# driver.net
KiCad netlist of a schematic drawn in EAGLE
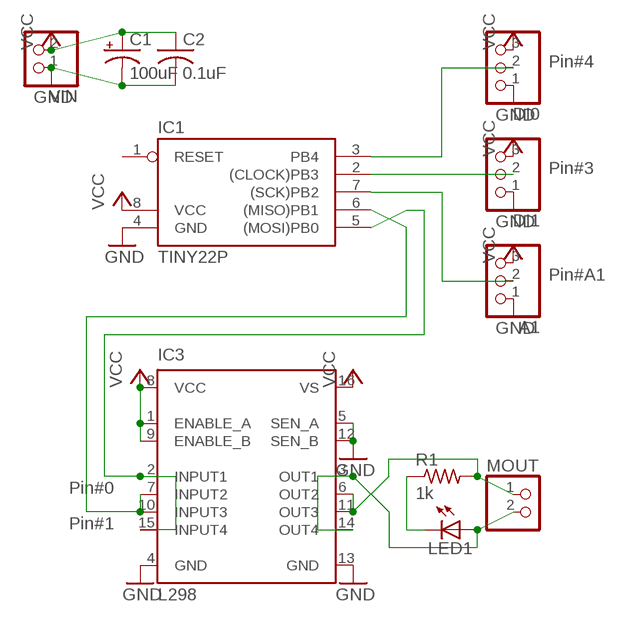
[diagram p0: schematic, sheet 1]

(export (version "E")
  (design (tool "Eeschema 10.0.6"))
  (components
    (comp (ref "A1")
      (value "PINHD-1X3")
      (footprint "eagle-import:1X03")
      (libsource (lib "eagle-import") (part "PINHD-1X3"))
    )
    (comp (ref "C1")
      (value "100uF")
      (footprint "eagle-import:E2,5-6E")
      (libsource (lib "eagle-import") (part "CPOL-USE2,5-6E"))
    )
    (comp (ref "C2")
      (value "0.1uF")
      (footprint "eagle-import:C025-025X050")
      (libsource (lib "eagle-import") (part "C-US025-025X050"))
    )
    (comp (ref "DI0")
      (value "PINHD-1X3")
      (footprint "eagle-import:1X03")
      (libsource (lib "eagle-import") (part "PINHD-1X3"))
    )
    (comp (ref "DI1")
      (value "PINHD-1X3")
      (footprint "eagle-import:1X03")
      (libsource (lib "eagle-import") (part "PINHD-1X3"))
    )
    (comp (ref "IC1")
      (value "TINY22P")
      (footprint "eagle-import:DIL08")
      (libsource (lib "eagle-import") (part "TINY22P"))
    )
    (comp (ref "IC3")
      (value "L298")
      (footprint "eagle-import:DIL16")
      (libsource (lib "eagle-import") (part "L298"))
    )
    (comp (ref "LED1")
      (value "LED5MM")
      (footprint "eagle-import:LED5MM")
      (libsource (lib "eagle-import") (part "LED5MM"))
    )
    (comp (ref "MOUT")
      (value "PINHD-1X2")
      (footprint "eagle-import:1X02")
      (libsource (lib "eagle-import") (part "PINHD-1X2"))
    )
    (comp (ref "R1")
      (value "1k")
      (footprint "eagle-import:0204V")
      (libsource (lib "eagle-import") (part "R-US_0204/2V"))
    )
    (comp (ref "VIN")
      (value "PINHD-1X2")
      (footprint "eagle-import:1X02")
      (libsource (lib "eagle-import") (part "PINHD-1X2"))
    )
  )
  (nets
    (net (code "1") (name "GND") (class "Default")
      (node (ref "A1") (pin "1") (pinfunction "1_1") (pintype "passive"))
      (node (ref "C1") (pin "-") (pinfunction "-_-") (pintype "passive"))
      (node (ref "C2") (pin "2") (pinfunction "2_2") (pintype "passive"))
      (node (ref "DI0") (pin "1") (pinfunction "1_1") (pintype "passive"))
      (node (ref "DI1") (pin "1") (pinfunction "1_1") (pintype "passive"))
      (node (ref "IC1") (pin "4") (pinfunction "GND_4") (pintype "power_in"))
      (node (ref "IC3") (pin "12") (pinfunction "SEN_B_12") (pintype "input"))
      (node (ref "IC3") (pin "13") (pinfunction "GND_13") (pintype "power_in"))
      (node (ref "IC3") (pin "4") (pinfunction "GND_4") (pintype "power_in"))
      (node (ref "IC3") (pin "5") (pinfunction "SEN_A_5") (pintype "input"))
      (node (ref "VIN") (pin "1") (pinfunction "1_1") (pintype "passive"))
    )
    (net (code "2") (name "Net-(IC1-(CLOCK)PB3)") (class "Default")
      (node (ref "DI1") (pin "2") (pinfunction "2_2") (pintype "passive"))
      (node (ref "IC1") (pin "2") (pinfunction "(CLOCK)PB3_2") (pintype "bidirectional"))
    )
    (net (code "3") (name "Net-(IC1-(MISO)PB1)") (class "Default")
      (node (ref "IC1") (pin "6") (pinfunction "(MISO)PB1_6") (pintype "bidirectional"))
      (node (ref "IC3") (pin "10") (pinfunction "INPUT3_10") (pintype "input"))
      (node (ref "IC3") (pin "7") (pinfunction "INPUT2_7") (pintype "input"))
    )
    (net (code "4") (name "Net-(IC1-(MOSI)PB0)") (class "Default")
      (node (ref "IC1") (pin "5") (pinfunction "(MOSI)PB0_5") (pintype "bidirectional"))
      (node (ref "IC3") (pin "15") (pinfunction "INPUT4_15") (pintype "input"))
      (node (ref "IC3") (pin "2") (pinfunction "INPUT1_2") (pintype "input"))
    )
    (net (code "5") (name "Net-(IC1-(SCK)PB2)") (class "Default")
      (node (ref "A1") (pin "2") (pinfunction "2_2") (pintype "passive"))
      (node (ref "IC1") (pin "7") (pinfunction "(SCK)PB2_7") (pintype "bidirectional"))
    )
    (net (code "6") (name "Net-(IC1-PB4)") (class "Default")
      (node (ref "DI0") (pin "2") (pinfunction "2_2") (pintype "passive"))
      (node (ref "IC1") (pin "3") (pinfunction "PB4_3") (pintype "bidirectional"))
    )
    (net (code "7") (name "Net-(IC3-OUT1)") (class "Default")
      (node (ref "IC3") (pin "14") (pinfunction "OUT4_14") (pintype "output"))
      (node (ref "IC3") (pin "3") (pinfunction "OUT1_3") (pintype "output"))
      (node (ref "LED1") (pin "A") (pinfunction "A_A") (pintype "passive"))
      (node (ref "MOUT") (pin "2") (pinfunction "2_2") (pintype "passive"))
    )
    (net (code "8") (name "Net-(IC3-OUT2)") (class "Default")
      (node (ref "IC3") (pin "11") (pinfunction "OUT3_11") (pintype "output"))
      (node (ref "IC3") (pin "6") (pinfunction "OUT2_6") (pintype "output"))
      (node (ref "MOUT") (pin "1") (pinfunction "1_1") (pintype "passive"))
      (node (ref "R1") (pin "2") (pinfunction "2_2") (pintype "passive"))
    )
    (net (code "9") (name "Net-(LED1-C)") (class "Default")
      (node (ref "LED1") (pin "K") (pinfunction "C_K") (pintype "passive"))
      (node (ref "R1") (pin "1") (pinfunction "1_1") (pintype "passive"))
    )
    (net (code "10") (name "VCC") (class "Default")
      (node (ref "A1") (pin "3") (pinfunction "3_3") (pintype "passive"))
      (node (ref "C1") (pin "+") (pinfunction "+_+") (pintype "passive"))
      (node (ref "C2") (pin "1") (pinfunction "1_1") (pintype "passive"))
      (node (ref "DI0") (pin "3") (pinfunction "3_3") (pintype "passive"))
      (node (ref "DI1") (pin "3") (pinfunction "3_3") (pintype "passive"))
      (node (ref "IC1") (pin "8") (pinfunction "VCC_8") (pintype "power_in"))
      (node (ref "IC3") (pin "1") (pinfunction "ENABLE_A_1") (pintype "input"))
      (node (ref "IC3") (pin "16") (pinfunction "VS_16") (pintype "power_in"))
      (node (ref "IC3") (pin "8") (pinfunction "VCC_8") (pintype "power_in"))
      (node (ref "IC3") (pin "9") (pinfunction "ENABLE_B_9") (pintype "input"))
      (node (ref "VIN") (pin "2") (pinfunction "2_2") (pintype "passive"))
    )
    (net (code "11") (name "unconnected-(IC1-RESET-Pad1)") (class "Default")
      (node (ref "IC1") (pin "1") (pinfunction "RESET_1") (pintype "input"))
    )
  )
)
